# Power.net
KiCad netlist of a schematic drawn in Altium Designer
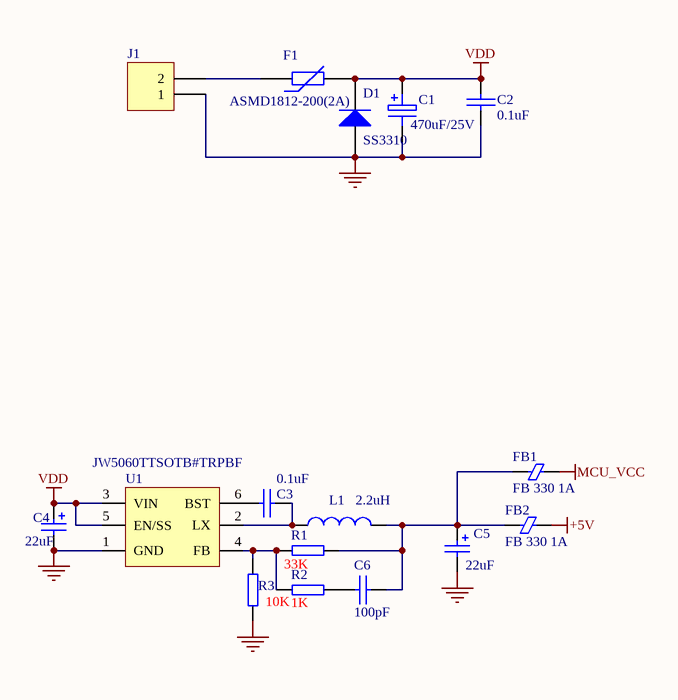
[diagram p0: Power.SchDoc]

(export (version "E")
  (design (tool "Eeschema 10.0.6"))
  (components
    (comp (ref "C1")
      (value "470uF/25V")
      (footprint "TPC4-M")
      (description "Electrolytic Capacitor")
      (libsource (lib "LdyLib") (part "ELECTRO1"))
    )
    (comp (ref "C2")
      (value "0.1uF")
      (footprint "C0603")
      (description "Capacitor")
      (libsource (lib "LDYLIB") (part "CAP"))
    )
    (comp (ref "C3")
      (value "0.1uF")
      (footprint "C0603")
      (description "Capacitor")
      (libsource (lib "LDYLIB") (part "CAP"))
    )
    (comp (ref "C4")
      (value "22uF")
      (footprint "HuaSenPcb-V2:C0603")
      (description "Polarized Capacitor (Axial)")
      (fields (field (name "PUBLISHER") "Altium Limited"))
      (libsource (lib "Miscellaneous Devices") (part "Cap Pol2"))
    )
    (comp (ref "C5")
      (value "22uF")
      (footprint "HuaSenPcb-V2:C0603")
      (description "Polarized Capacitor (Axial)")
      (fields (field (name "PUBLISHER") "Altium Limited"))
      (libsource (lib "Miscellaneous Devices") (part "Cap Pol2"))
    )
    (comp (ref "C6")
      (value "100pF")
      (footprint "C0603")
      (description "Capacitor")
      (libsource (lib "LDYLIB") (part "CAP"))
    )
    (comp (ref "D1")
      (value "SS3310")
      (footprint "SO-0.4")
      (description "Default Diode")
      (fields (field (name "PUBLISHER") "Altium Limited"))
      (libsource (lib "Miscellaneous Devices") (part "Diode"))
    )
    (comp (ref "F1")
      (value "ASMD1812-200(2A)")
      (footprint "FS1812")
      (description "Varistor (Voltage-Sensitive Resistor)")
      (fields (field (name "PUBLISHER") "Altium Limited"))
      (libsource (lib "Miscellaneous Devices") (part "Res Varistor"))
    )
    (comp (ref "FB1")
      (value "FB 330 1A")
      (footprint "R0603")
      (description "磁珠电感100M")
      (libsource (lib "LDYLIB") (part "FB"))
    )
    (comp (ref "FB2")
      (value "FB 330 1A")
      (footprint "R0603")
      (description "磁珠电感100M")
      (libsource (lib "LDYLIB") (part "FB"))
    )
    (comp (ref "J1")
      (value "Header 2")
      (footprint "JITE2_1")
      (description "Header, 2-Pin")
      (fields (field (name "PUBLISHER") "Altium Limited"))
      (libsource (lib "Miscellaneous Connectors") (part "Header 2"))
    )
    (comp (ref "L1")
      (value "2.2uH")
      (footprint "2220")
      (description "MS74-150MT")
      (fields (field (name "型号") "2.2uH"))
      (libsource (lib "LDYLIB") (part "L"))
    )
    (comp (ref "R1")
      (value "33K")
      (footprint "R0603")
      (description "RES2")
      (libsource (lib "LDYLIB") (part "RES9"))
    )
    (comp (ref "R2")
      (value "1K")
      (footprint "R0603")
      (description "RES2")
      (libsource (lib "LDYLIB") (part "RES9"))
    )
    (comp (ref "R3")
      (value "10K")
      (footprint "R0603")
      (description "RES2")
      (libsource (lib "LDYLIB") (part "RES9"))
    )
    (comp (ref "U1")
      (value "JW5060TTSOTB#TRPBF")
      (footprint "SOT23-6")
      (libsource (lib "原理图库") (part "XC9280"))
    )
  )
  (nets
    (net (code "1") (name "+5V") (class "Default")
      (node (ref "FB2") (pin "2") (pinfunction "2_2") (pintype "passive"))
    )
    (net (code "2") (name "GND") (class "Default")
      (node (ref "C1") (pin "2") (pinfunction "2_2") (pintype "passive"))
      (node (ref "C2") (pin "2") (pinfunction "2_2") (pintype "passive"))
      (node (ref "C4") (pin "2") (pinfunction "2_2") (pintype "passive"))
      (node (ref "C5") (pin "2") (pinfunction "2_2") (pintype "passive"))
      (node (ref "D1") (pin "A") (pinfunction "A_A") (pintype "passive"))
      (node (ref "J1") (pin "1") (pinfunction "1_1") (pintype "passive"))
      (node (ref "R3") (pin "1") (pinfunction "1_1") (pintype "passive"))
      (node (ref "U1") (pin "1") (pinfunction "GND_1") (pintype "passive"))
    )
    (net (code "3") (name "MCU_VCC") (class "Default")
      (node (ref "FB1") (pin "2") (pinfunction "2_2") (pintype "passive"))
    )
    (net (code "4") (name "Net-(C5-Pad1)") (class "Default")
      (node (ref "C5") (pin "1") (pinfunction "1_1") (pintype "passive"))
      (node (ref "C6") (pin "2") (pinfunction "2_2") (pintype "passive"))
      (node (ref "FB1") (pin "1") (pinfunction "1_1") (pintype "passive"))
      (node (ref "FB2") (pin "1") (pinfunction "1_1") (pintype "passive"))
      (node (ref "L1") (pin "2") (pinfunction "2_2") (pintype "passive"))
      (node (ref "R1") (pin "1") (pinfunction "1_1") (pintype "passive"))
    )
    (net (code "5") (name "Net-(C6-Pad1)") (class "Default")
      (node (ref "C6") (pin "1") (pinfunction "1_1") (pintype "passive"))
      (node (ref "R2") (pin "1") (pinfunction "1_1") (pintype "passive"))
    )
    (net (code "6") (name "Net-(F1-Pad1)") (class "Default")
      (node (ref "F1") (pin "1") (pinfunction "1_1") (pintype "passive"))
      (node (ref "J1") (pin "2") (pinfunction "2_2") (pintype "passive"))
    )
    (net (code "7") (name "Net-(U1-BST)") (class "Default")
      (node (ref "C3") (pin "2") (pinfunction "2_2") (pintype "passive"))
      (node (ref "U1") (pin "6") (pinfunction "BST_6") (pintype "passive"))
    )
    (net (code "8") (name "Net-(U1-FB)") (class "Default")
      (node (ref "R1") (pin "2") (pinfunction "2_2") (pintype "passive"))
      (node (ref "R2") (pin "2") (pinfunction "2_2") (pintype "passive"))
      (node (ref "R3") (pin "2") (pinfunction "2_2") (pintype "passive"))
      (node (ref "U1") (pin "4") (pinfunction "FB_4") (pintype "passive"))
    )
    (net (code "9") (name "Net-(U1-LX)") (class "Default")
      (node (ref "C3") (pin "1") (pinfunction "1_1") (pintype "passive"))
      (node (ref "L1") (pin "1") (pinfunction "1_1") (pintype "passive"))
      (node (ref "U1") (pin "2") (pinfunction "LX_2") (pintype "passive"))
    )
    (net (code "10") (name "VDD") (class "Default")
      (node (ref "C1") (pin "1") (pinfunction "1_1") (pintype "passive"))
      (node (ref "C2") (pin "1") (pinfunction "1_1") (pintype "passive"))
      (node (ref "C4") (pin "1") (pinfunction "1_1") (pintype "passive"))
      (node (ref "D1") (pin "K") (pinfunction "K_K") (pintype "passive"))
      (node (ref "F1") (pin "2") (pinfunction "2_2") (pintype "passive"))
      (node (ref "U1") (pin "3") (pinfunction "VIN_3") (pintype "passive"))
      (node (ref "U1") (pin "5") (pinfunction "EN/SS_5") (pintype "passive"))
    )
  )
)
